# VHF-Superregen.net
KiCad netlist of a schematic drawn in EAGLE
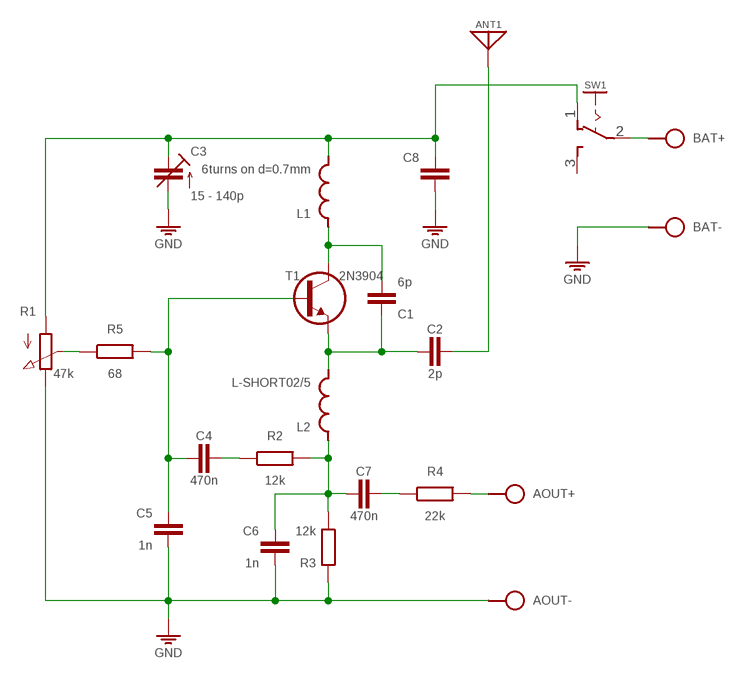
[diagram p0: schematic, sheet 1]

(export (version "E")
  (design (tool "Eeschema 10.0.6"))
  (components
    (comp (ref "ANT1")
      (value "ANT")
      (footprint "eagle-import:SPAD")
      (libsource (lib "eagle-import") (part "ANT"))
    )
    (comp (ref "AOUT+")
      (value "SPAD")
      (footprint "eagle-import:SPAD")
      (libsource (lib "eagle-import") (part "SPAD"))
    )
    (comp (ref "AOUT-")
      (value "SPAD")
      (footprint "eagle-import:SPAD")
      (libsource (lib "eagle-import") (part "SPAD"))
    )
    (comp (ref "BAT+")
      (value "SPAD")
      (footprint "eagle-import:SPAD")
      (libsource (lib "eagle-import") (part "SPAD"))
    )
    (comp (ref "BAT-")
      (value "SPAD")
      (footprint "eagle-import:SPAD")
      (libsource (lib "eagle-import") (part "SPAD"))
    )
    (comp (ref "C1")
      (value "6p")
      (footprint "eagle-import:C050-020X036")
      (libsource (lib "eagle-import") (part "C050-020X036"))
    )
    (comp (ref "C2")
      (value "2p")
      (footprint "eagle-import:C025-015X024")
      (libsource (lib "eagle-import") (part "C025-015X024"))
    )
    (comp (ref "C3")
      (value "15 - 140p")
      (footprint "eagle-import:TRIM-2222-808")
      (libsource (lib "eagle-import") (part "C-TR-PH201272222-808-2PINB"))
    )
    (comp (ref "C4")
      (value "470n")
      (footprint "eagle-import:C025-015X024")
      (libsource (lib "eagle-import") (part "C025-015X024"))
    )
    (comp (ref "C5")
      (value "1n")
      (footprint "eagle-import:C025-020X036")
      (libsource (lib "eagle-import") (part "C025-020X036"))
    )
    (comp (ref "C6")
      (value "1n")
      (footprint "eagle-import:C025-020X036")
      (libsource (lib "eagle-import") (part "C025-020X036"))
    )
    (comp (ref "C7")
      (value "470n")
      (footprint "eagle-import:C025-015X024")
      (libsource (lib "eagle-import") (part "C025-015X024"))
    )
    (comp (ref "C8")
      (value "C050-025X075")
      (footprint "eagle-import:C050-025X075")
      (libsource (lib "eagle-import") (part "C050-025X075"))
    )
    (comp (ref "L1")
      (value "6turns on d=0.7mm")
      (footprint "eagle-import:L-04_7V")
      (libsource (lib "eagle-import") (part "L-SHORT04/7"))
    )
    (comp (ref "L2")
      (value "L-SHORT02/5")
      (footprint "eagle-import:L-02_5V")
      (libsource (lib "eagle-import") (part "L-SHORT02/5"))
    )
    (comp (ref "R1")
      (value "47k")
      (footprint "eagle-import:POT")
      (libsource (lib "eagle-import") (part "POT"))
    )
    (comp (ref "R2")
      (value "12k")
      (footprint "eagle-import:0202_7")
      (libsource (lib "eagle-import") (part "R0202/7"))
    )
    (comp (ref "R3")
      (value "12k")
      (footprint "eagle-import:0202_7")
      (libsource (lib "eagle-import") (part "R0202/7"))
    )
    (comp (ref "R4")
      (value "22k")
      (footprint "eagle-import:0202_7")
      (libsource (lib "eagle-import") (part "R0202/7"))
    )
    (comp (ref "R5")
      (value "68")
      (footprint "eagle-import:0202_7")
      (libsource (lib "eagle-import") (part "R0202/7"))
    )
    (comp (ref "SW1")
      (value "SL-SW-1P-2T-H")
      (footprint "eagle-import:SLSW-1P2T-H")
      (libsource (lib "eagle-import") (part "SL-SW-1P-2T-H"))
    )
    (comp (ref "T1")
      (value "2N3904")
      (footprint "eagle-import:TO92")
      (libsource (lib "eagle-import") (part "2N3904"))
    )
  )
  (nets
    (net (code "1") (name "GND") (class "Default")
      (node (ref "AOUT-") (pin "1") (pinfunction "P$1_1") (pintype "bidirectional"))
      (node (ref "BAT-") (pin "1") (pinfunction "P$1_1") (pintype "bidirectional"))
      (node (ref "C3") (pin "2") (pinfunction "A_2") (pintype "passive"))
      (node (ref "C5") (pin "2") (pinfunction "2_2") (pintype "passive"))
      (node (ref "C6") (pin "2") (pinfunction "2_2") (pintype "passive"))
      (node (ref "C8") (pin "2") (pinfunction "2_2") (pintype "passive"))
      (node (ref "R1") (pin "3") (pinfunction "E_3") (pintype "passive"))
      (node (ref "R3") (pin "2") (pinfunction "2_2") (pintype "passive"))
    )
    (net (code "2") (name "Net-(ANT1-Pad1)") (class "Default")
      (node (ref "ANT1") (pin "1") (pinfunction "1_1") (pintype "output"))
      (node (ref "C2") (pin "1") (pinfunction "1_1") (pintype "passive"))
    )
    (net (code "3") (name "Net-(AOUT+-P$1)") (class "Default")
      (node (ref "AOUT+") (pin "1") (pinfunction "P$1_1") (pintype "bidirectional"))
      (node (ref "R4") (pin "2") (pinfunction "2_2") (pintype "passive"))
    )
    (net (code "4") (name "Net-(BAT+-P$1)") (class "Default")
      (node (ref "BAT+") (pin "1") (pinfunction "P$1_1") (pintype "bidirectional"))
      (node (ref "SW1") (pin "2") (pinfunction "P_2") (pintype "passive"))
    )
    (net (code "5") (name "Net-(C3-E)") (class "Default")
      (node (ref "C3") (pin "3") (pinfunction "E_3") (pintype "passive"))
      (node (ref "C8") (pin "1") (pinfunction "1_1") (pintype "passive"))
      (node (ref "L1") (pin "2") (pinfunction "2_2") (pintype "passive"))
      (node (ref "R1") (pin "1") (pinfunction "A_1") (pintype "passive"))
      (node (ref "SW1") (pin "1") (pinfunction "O_1") (pintype "passive"))
    )
    (net (code "6") (name "Net-(C4-Pad1)") (class "Default")
      (node (ref "C4") (pin "1") (pinfunction "1_1") (pintype "passive"))
      (node (ref "R2") (pin "1") (pinfunction "1_1") (pintype "passive"))
    )
    (net (code "7") (name "Net-(C6-Pad1)") (class "Default")
      (node (ref "C6") (pin "1") (pinfunction "1_1") (pintype "passive"))
      (node (ref "C7") (pin "2") (pinfunction "2_2") (pintype "passive"))
      (node (ref "L2") (pin "1") (pinfunction "1_1") (pintype "passive"))
      (node (ref "R2") (pin "2") (pinfunction "2_2") (pintype "passive"))
      (node (ref "R3") (pin "1") (pinfunction "1_1") (pintype "passive"))
    )
    (net (code "8") (name "Net-(C7-Pad1)") (class "Default")
      (node (ref "C7") (pin "1") (pinfunction "1_1") (pintype "passive"))
      (node (ref "R4") (pin "1") (pinfunction "1_1") (pintype "passive"))
    )
    (net (code "9") (name "Net-(R1-S)") (class "Default")
      (node (ref "R1") (pin "2") (pinfunction "S_2") (pintype "passive"))
      (node (ref "R5") (pin "1") (pinfunction "1_1") (pintype "passive"))
    )
    (net (code "10") (name "Net-(T1-B)") (class "Default")
      (node (ref "C4") (pin "2") (pinfunction "2_2") (pintype "passive"))
      (node (ref "C5") (pin "1") (pinfunction "1_1") (pintype "passive"))
      (node (ref "R5") (pin "2") (pinfunction "2_2") (pintype "passive"))
      (node (ref "T1") (pin "2") (pinfunction "B_2") (pintype "passive"))
    )
    (net (code "11") (name "Net-(T1-C)") (class "Default")
      (node (ref "C1") (pin "2") (pinfunction "2_2") (pintype "passive"))
      (node (ref "L1") (pin "1") (pinfunction "1_1") (pintype "passive"))
      (node (ref "T1") (pin "3") (pinfunction "C_3") (pintype "passive"))
    )
    (net (code "12") (name "Net-(T1-E)") (class "Default")
      (node (ref "C1") (pin "1") (pinfunction "1_1") (pintype "passive"))
      (node (ref "C2") (pin "2") (pinfunction "2_2") (pintype "passive"))
      (node (ref "L2") (pin "2") (pinfunction "2_2") (pintype "passive"))
      (node (ref "T1") (pin "1") (pinfunction "E_1") (pintype "passive"))
    )
    (net (code "13") (name "unconnected-(SW1-S-Pad3)") (class "Default")
      (node (ref "SW1") (pin "3") (pinfunction "S_3") (pintype "passive"))
    )
  )
)
